# TX.net
KiCad netlist of a schematic drawn in EAGLE
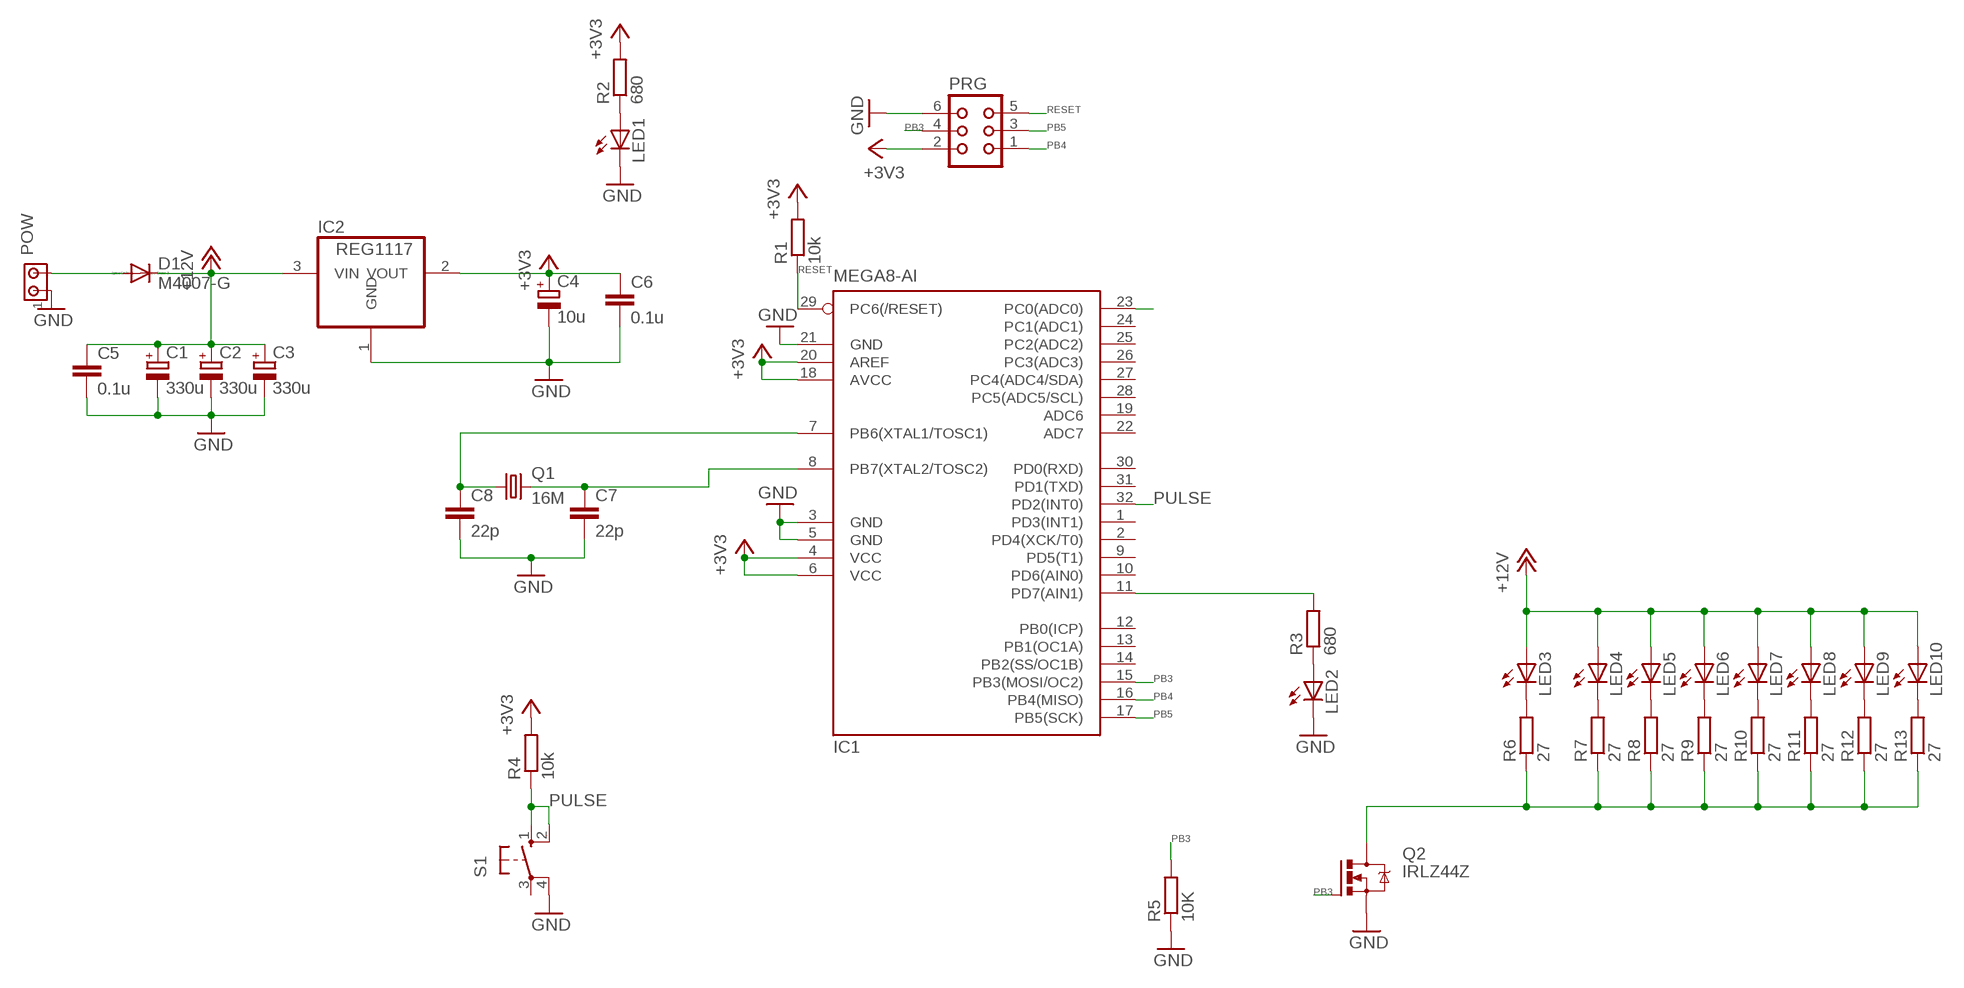
[diagram p0: schematic, sheet 1]

(export (version "E")
  (design (tool "Eeschema 10.0.6"))
  (components
    (comp (ref "C1")
      (value "330u")
      (footprint "eagle-import:140CLH-1010")
      (libsource (lib "eagle-import") (part "CPOL-EU140CLH-1010"))
    )
    (comp (ref "C2")
      (value "330u")
      (footprint "eagle-import:140CLH-1010")
      (libsource (lib "eagle-import") (part "CPOL-EU140CLH-1010"))
    )
    (comp (ref "C3")
      (value "330u")
      (footprint "eagle-import:140CLH-1010")
      (libsource (lib "eagle-import") (part "CPOL-EU140CLH-1010"))
    )
    (comp (ref "C4")
      (value "10u")
      (footprint "eagle-import:140CLH-0810")
      (libsource (lib "eagle-import") (part "CPOL-EU140CLH-0810"))
    )
    (comp (ref "C5")
      (value "0.1u")
      (footprint "eagle-import:C0402")
      (libsource (lib "eagle-import") (part "C-EUC0402"))
    )
    (comp (ref "C6")
      (value "0.1u")
      (footprint "eagle-import:C0402")
      (libsource (lib "eagle-import") (part "C-EUC0402"))
    )
    (comp (ref "C7")
      (value "22p")
      (footprint "eagle-import:C0805")
      (libsource (lib "eagle-import") (part "C-EUC0805"))
    )
    (comp (ref "C8")
      (value "22p")
      (footprint "eagle-import:C0805")
      (libsource (lib "eagle-import") (part "C-EUC0805"))
    )
    (comp (ref "D1")
      (value "M4007-G")
      (footprint "eagle-import:SOD-123_MINI-SMA")
      (libsource (lib "eagle-import") (part "CGRM400-G7"))
    )
    (comp (ref "IC1")
      (value "MEGA8-AI")
      (footprint "eagle-import:TQFP32-08")
      (fields (field (name "MPN") "ATMEGA8-16AU"))
      (libsource (lib "eagle-import") (part "MEGA8-AI"))
    )
    (comp (ref "IC2")
      (value "REG1117")
      (footprint "eagle-import:SOT223")
      (libsource (lib "eagle-import") (part "REG1117"))
    )
    (comp (ref "LED1")
      (value "LED5MM")
      (footprint "eagle-import:LED5MM")
      (libsource (lib "eagle-import") (part "LED5MM"))
    )
    (comp (ref "LED2")
      (value "LED5MM")
      (footprint "eagle-import:LED5MM")
      (libsource (lib "eagle-import") (part "LED5MM"))
    )
    (comp (ref "LED3")
      (value "LED5MM")
      (footprint "eagle-import:LED5MM")
      (libsource (lib "eagle-import") (part "LED5MM"))
    )
    (comp (ref "LED4")
      (value "LED5MM")
      (footprint "eagle-import:LED5MM")
      (libsource (lib "eagle-import") (part "LED5MM"))
    )
    (comp (ref "LED5")
      (value "LED5MM")
      (footprint "eagle-import:LED5MM")
      (libsource (lib "eagle-import") (part "LED5MM"))
    )
    (comp (ref "LED6")
      (value "LED5MM")
      (footprint "eagle-import:LED5MM")
      (libsource (lib "eagle-import") (part "LED5MM"))
    )
    (comp (ref "LED7")
      (value "LED5MM")
      (footprint "eagle-import:LED5MM")
      (libsource (lib "eagle-import") (part "LED5MM"))
    )
    (comp (ref "LED8")
      (value "LED5MM")
      (footprint "eagle-import:LED5MM")
      (libsource (lib "eagle-import") (part "LED5MM"))
    )
    (comp (ref "LED9")
      (value "LED5MM")
      (footprint "eagle-import:LED5MM")
      (libsource (lib "eagle-import") (part "LED5MM"))
    )
    (comp (ref "LED10")
      (value "LED5MM")
      (footprint "eagle-import:LED5MM")
      (libsource (lib "eagle-import") (part "LED5MM"))
    )
    (comp (ref "POW")
      (value "MTA02-100")
      (footprint "eagle-import:10X02MTA")
      (libsource (lib "eagle-import") (part "MTA02-100"))
    )
    (comp (ref "PRG")
      (value "CON06")
      (footprint "eagle-import:CON06")
      (libsource (lib "eagle-import") (part "CON06"))
    )
    (comp (ref "Q1")
      (value "16M")
      (footprint "eagle-import:HC49UP")
      (libsource (lib "eagle-import") (part "CRYSTALHC49UP"))
    )
    (comp (ref "Q2")
      (value "IRLZ44Z")
      (footprint "eagle-import:TO220BH")
      (libsource (lib "eagle-import") (part "IRLZ44Z"))
    )
    (comp (ref "R1")
      (value "10k")
      (footprint "eagle-import:M1206")
      (libsource (lib "eagle-import") (part "R-EU_M1206"))
    )
    (comp (ref "R2")
      (value "680")
      (footprint "eagle-import:M1206")
      (libsource (lib "eagle-import") (part "R-EU_M1206"))
    )
    (comp (ref "R3")
      (value "680")
      (footprint "eagle-import:M1206")
      (libsource (lib "eagle-import") (part "R-EU_M1206"))
    )
    (comp (ref "R4")
      (value "10k")
      (footprint "eagle-import:M1206")
      (libsource (lib "eagle-import") (part "R-EU_M1206"))
    )
    (comp (ref "R5")
      (value "10K")
      (footprint "eagle-import:M1206")
      (libsource (lib "eagle-import") (part "R-EU_M1206"))
    )
    (comp (ref "R6")
      (value "27")
      (footprint "eagle-import:0204_7")
      (libsource (lib "eagle-import") (part "R-EU_0204/7"))
    )
    (comp (ref "R7")
      (value "27")
      (footprint "eagle-import:0204_7")
      (libsource (lib "eagle-import") (part "R-EU_0204/7"))
    )
    (comp (ref "R8")
      (value "27")
      (footprint "eagle-import:0204_7")
      (libsource (lib "eagle-import") (part "R-EU_0204/7"))
    )
    (comp (ref "R9")
      (value "27")
      (footprint "eagle-import:0204_7")
      (libsource (lib "eagle-import") (part "R-EU_0204/7"))
    )
    (comp (ref "R10")
      (value "27")
      (footprint "eagle-import:0204_7")
      (libsource (lib "eagle-import") (part "R-EU_0204/7"))
    )
    (comp (ref "R11")
      (value "27")
      (footprint "eagle-import:0204_7")
      (libsource (lib "eagle-import") (part "R-EU_0204/7"))
    )
    (comp (ref "R12")
      (value "27")
      (footprint "eagle-import:0204_7")
      (libsource (lib "eagle-import") (part "R-EU_0204/7"))
    )
    (comp (ref "R13")
      (value "27")
      (footprint "eagle-import:0204_7")
      (libsource (lib "eagle-import") (part "R-EU_0204/7"))
    )
    (comp (ref "S1")
      (value "10-XX")
      (footprint "eagle-import:B3F-10XX")
      (fields (field (name "MPN") "B3F-1000"))
      (libsource (lib "eagle-import") (part "10-XX"))
    )
  )
  (nets
    (net (code "1") (name "+3V3") (class "Default")
      (node (ref "C4") (pin "+") (pinfunction "+_+") (pintype "passive"))
      (node (ref "C6") (pin "1") (pinfunction "1_1") (pintype "passive"))
      (node (ref "IC1") (pin "18") (pinfunction "AVCC_18") (pintype "power_in"))
      (node (ref "IC1") (pin "20") (pinfunction "AREF_20") (pintype "passive"))
      (node (ref "IC1") (pin "4") (pinfunction "VCC_4") (pintype "power_in"))
      (node (ref "IC1") (pin "6") (pinfunction "VCC_6") (pintype "power_in"))
      (node (ref "IC2") (pin "2") (pinfunction "VOUT_2") (pintype "output"))
      (node (ref "PRG") (pin "2") (pinfunction "2_2") (pintype "passive"))
      (node (ref "R1") (pin "2") (pinfunction "2_2") (pintype "passive"))
      (node (ref "R2") (pin "2") (pinfunction "2_2") (pintype "passive"))
      (node (ref "R4") (pin "2") (pinfunction "2_2") (pintype "passive"))
    )
    (net (code "2") (name "+12V") (class "Default")
      (node (ref "C1") (pin "+") (pinfunction "+_+") (pintype "passive"))
      (node (ref "C2") (pin "+") (pinfunction "+_+") (pintype "passive"))
      (node (ref "C3") (pin "+") (pinfunction "+_+") (pintype "passive"))
      (node (ref "C5") (pin "1") (pinfunction "1_1") (pintype "passive"))
      (node (ref "D1") (pin "C") (pinfunction "C_C") (pintype "passive"))
      (node (ref "IC2") (pin "3") (pinfunction "VIN_3") (pintype "input"))
      (node (ref "LED10") (pin "A") (pinfunction "A_A") (pintype "passive"))
      (node (ref "LED3") (pin "A") (pinfunction "A_A") (pintype "passive"))
      (node (ref "LED4") (pin "A") (pinfunction "A_A") (pintype "passive"))
      (node (ref "LED5") (pin "A") (pinfunction "A_A") (pintype "passive"))
      (node (ref "LED6") (pin "A") (pinfunction "A_A") (pintype "passive"))
      (node (ref "LED7") (pin "A") (pinfunction "A_A") (pintype "passive"))
      (node (ref "LED8") (pin "A") (pinfunction "A_A") (pintype "passive"))
      (node (ref "LED9") (pin "A") (pinfunction "A_A") (pintype "passive"))
    )
    (net (code "3") (name "/PB3") (class "Default")
      (node (ref "IC1") (pin "15") (pinfunction "PB3(MOSI/OC2)_15") (pintype "bidirectional"))
      (node (ref "PRG") (pin "4") (pinfunction "4_4") (pintype "passive"))
      (node (ref "Q2") (pin "G") (pinfunction "G_G") (pintype "passive"))
      (node (ref "R5") (pin "2") (pinfunction "2_2") (pintype "passive"))
    )
    (net (code "4") (name "/PB4") (class "Default")
      (node (ref "IC1") (pin "16") (pinfunction "PB4(MISO)_16") (pintype "bidirectional"))
      (node (ref "PRG") (pin "1") (pinfunction "1_1") (pintype "passive"))
    )
    (net (code "5") (name "/PB5") (class "Default")
      (node (ref "IC1") (pin "17") (pinfunction "PB5(SCK)_17") (pintype "bidirectional"))
      (node (ref "PRG") (pin "3") (pinfunction "3_3") (pintype "passive"))
    )
    (net (code "6") (name "/PULSE") (class "Default")
      (node (ref "IC1") (pin "32") (pinfunction "PD2(INT0)_32") (pintype "bidirectional"))
      (node (ref "R4") (pin "1") (pinfunction "1_1") (pintype "passive"))
      (node (ref "S1") (pin "1") (pinfunction "S_1") (pintype "passive"))
      (node (ref "S1") (pin "2") (pinfunction "S1_2") (pintype "passive"))
    )
    (net (code "7") (name "/RESET") (class "Default")
      (node (ref "IC1") (pin "29") (pinfunction "PC6(/RESET)_29") (pintype "bidirectional"))
      (node (ref "PRG") (pin "5") (pinfunction "5_5") (pintype "passive"))
      (node (ref "R1") (pin "1") (pinfunction "1_1") (pintype "passive"))
    )
    (net (code "8") (name "GND") (class "Default")
      (node (ref "C1") (pin "-") (pinfunction "-_-") (pintype "passive"))
      (node (ref "C2") (pin "-") (pinfunction "-_-") (pintype "passive"))
      (node (ref "C3") (pin "-") (pinfunction "-_-") (pintype "passive"))
      (node (ref "C4") (pin "-") (pinfunction "-_-") (pintype "passive"))
      (node (ref "C5") (pin "2") (pinfunction "2_2") (pintype "passive"))
      (node (ref "C6") (pin "2") (pinfunction "2_2") (pintype "passive"))
      (node (ref "C7") (pin "2") (pinfunction "2_2") (pintype "passive"))
      (node (ref "C8") (pin "2") (pinfunction "2_2") (pintype "passive"))
      (node (ref "IC1") (pin "21") (pinfunction "GND_21") (pintype "power_in"))
      (node (ref "IC1") (pin "3") (pinfunction "GND_3") (pintype "power_in"))
      (node (ref "IC1") (pin "5") (pinfunction "GND_5") (pintype "power_in"))
      (node (ref "IC2") (pin "1") (pinfunction "GND_1") (pintype "power_in"))
      (node (ref "LED1") (pin "K") (pinfunction "C_K") (pintype "passive"))
      (node (ref "LED2") (pin "K") (pinfunction "C_K") (pintype "passive"))
      (node (ref "POW") (pin "1") (pinfunction "1_1") (pintype "passive"))
      (node (ref "PRG") (pin "6") (pinfunction "6_6") (pintype "passive"))
      (node (ref "Q2") (pin "S") (pinfunction "S_S") (pintype "passive"))
      (node (ref "R5") (pin "1") (pinfunction "1_1") (pintype "passive"))
      (node (ref "S1") (pin "4") (pinfunction "P1_4") (pintype "passive"))
    )
    (net (code "9") (name "Net-(D1-PadA)") (class "Default")
      (node (ref "D1") (pin "A") (pinfunction "A_A") (pintype "passive"))
      (node (ref "POW") (pin "2") (pinfunction "2_2") (pintype "passive"))
    )
    (net (code "10") (name "Net-(IC1-PB6(XTAL1{slash}TOSC1))") (class "Default")
      (node (ref "C8") (pin "1") (pinfunction "1_1") (pintype "passive"))
      (node (ref "IC1") (pin "7") (pinfunction "PB6(XTAL1/TOSC1)_7") (pintype "bidirectional"))
      (node (ref "Q1") (pin "1") (pinfunction "1_1") (pintype "passive"))
    )
    (net (code "11") (name "Net-(IC1-PB7(XTAL2{slash}TOSC2))") (class "Default")
      (node (ref "C7") (pin "1") (pinfunction "1_1") (pintype "passive"))
      (node (ref "IC1") (pin "8") (pinfunction "PB7(XTAL2/TOSC2)_8") (pintype "bidirectional"))
      (node (ref "Q1") (pin "2") (pinfunction "2_2") (pintype "passive"))
    )
    (net (code "12") (name "Net-(IC1-PD7(AIN1))") (class "Default")
      (node (ref "IC1") (pin "11") (pinfunction "PD7(AIN1)_11") (pintype "bidirectional"))
      (node (ref "R3") (pin "2") (pinfunction "2_2") (pintype "passive"))
    )
    (net (code "13") (name "Net-(LED1-PadA)") (class "Default")
      (node (ref "LED1") (pin "A") (pinfunction "A_A") (pintype "passive"))
      (node (ref "R2") (pin "1") (pinfunction "1_1") (pintype "passive"))
    )
    (net (code "14") (name "Net-(LED2-PadA)") (class "Default")
      (node (ref "LED2") (pin "A") (pinfunction "A_A") (pintype "passive"))
      (node (ref "R3") (pin "1") (pinfunction "1_1") (pintype "passive"))
    )
    (net (code "15") (name "Net-(LED3-C)") (class "Default")
      (node (ref "LED3") (pin "K") (pinfunction "C_K") (pintype "passive"))
      (node (ref "R6") (pin "2") (pinfunction "2_2") (pintype "passive"))
    )
    (net (code "16") (name "Net-(LED4-C)") (class "Default")
      (node (ref "LED4") (pin "K") (pinfunction "C_K") (pintype "passive"))
      (node (ref "R7") (pin "2") (pinfunction "2_2") (pintype "passive"))
    )
    (net (code "17") (name "Net-(LED5-C)") (class "Default")
      (node (ref "LED5") (pin "K") (pinfunction "C_K") (pintype "passive"))
      (node (ref "R8") (pin "2") (pinfunction "2_2") (pintype "passive"))
    )
    (net (code "18") (name "Net-(LED6-C)") (class "Default")
      (node (ref "LED6") (pin "K") (pinfunction "C_K") (pintype "passive"))
      (node (ref "R9") (pin "2") (pinfunction "2_2") (pintype "passive"))
    )
    (net (code "19") (name "Net-(LED7-C)") (class "Default")
      (node (ref "LED7") (pin "K") (pinfunction "C_K") (pintype "passive"))
      (node (ref "R10") (pin "2") (pinfunction "2_2") (pintype "passive"))
    )
    (net (code "20") (name "Net-(LED8-C)") (class "Default")
      (node (ref "LED8") (pin "K") (pinfunction "C_K") (pintype "passive"))
      (node (ref "R11") (pin "2") (pinfunction "2_2") (pintype "passive"))
    )
    (net (code "21") (name "Net-(LED9-C)") (class "Default")
      (node (ref "LED9") (pin "K") (pinfunction "C_K") (pintype "passive"))
      (node (ref "R12") (pin "2") (pinfunction "2_2") (pintype "passive"))
    )
    (net (code "22") (name "Net-(LED10-C)") (class "Default")
      (node (ref "LED10") (pin "K") (pinfunction "C_K") (pintype "passive"))
      (node (ref "R13") (pin "2") (pinfunction "2_2") (pintype "passive"))
    )
    (net (code "23") (name "Net-(Q2-PadD)") (class "Default")
      (node (ref "Q2") (pin "D") (pinfunction "D_D") (pintype "passive"))
      (node (ref "R10") (pin "1") (pinfunction "1_1") (pintype "passive"))
      (node (ref "R11") (pin "1") (pinfunction "1_1") (pintype "passive"))
      (node (ref "R12") (pin "1") (pinfunction "1_1") (pintype "passive"))
      (node (ref "R13") (pin "1") (pinfunction "1_1") (pintype "passive"))
      (node (ref "R6") (pin "1") (pinfunction "1_1") (pintype "passive"))
      (node (ref "R7") (pin "1") (pinfunction "1_1") (pintype "passive"))
      (node (ref "R8") (pin "1") (pinfunction "1_1") (pintype "passive"))
      (node (ref "R9") (pin "1") (pinfunction "1_1") (pintype "passive"))
    )
    (net (code "24") (name "unconnected-(IC1-ADC6-Pad19)") (class "Default")
      (node (ref "IC1") (pin "19") (pinfunction "ADC6_19") (pintype "bidirectional"))
    )
    (net (code "25") (name "unconnected-(IC1-ADC7-Pad22)") (class "Default")
      (node (ref "IC1") (pin "22") (pinfunction "ADC7_22") (pintype "bidirectional"))
    )
    (net (code "26") (name "unconnected-(IC1-PB0(ICP)-Pad12)") (class "Default")
      (node (ref "IC1") (pin "12") (pinfunction "PB0(ICP)_12") (pintype "bidirectional"))
    )
    (net (code "27") (name "unconnected-(IC1-PB1(OC1A)-Pad13)") (class "Default")
      (node (ref "IC1") (pin "13") (pinfunction "PB1(OC1A)_13") (pintype "bidirectional"))
    )
    (net (code "28") (name "unconnected-(IC1-PB2(SS{slash}OC1B)-Pad14)") (class "Default")
      (node (ref "IC1") (pin "14") (pinfunction "PB2(SS/OC1B)_14") (pintype "bidirectional"))
    )
    (net (code "29") (name "unconnected-(IC1-PC0(ADC0)-Pad23)") (class "Default")
      (node (ref "IC1") (pin "23") (pinfunction "PC0(ADC0)_23") (pintype "bidirectional"))
    )
    (net (code "30") (name "unconnected-(IC1-PC1(ADC1)-Pad24)") (class "Default")
      (node (ref "IC1") (pin "24") (pinfunction "PC1(ADC1)_24") (pintype "bidirectional"))
    )
    (net (code "31") (name "unconnected-(IC1-PC2(ADC2)-Pad25)") (class "Default")
      (node (ref "IC1") (pin "25") (pinfunction "PC2(ADC2)_25") (pintype "bidirectional"))
    )
    (net (code "32") (name "unconnected-(IC1-PC3(ADC3)-Pad26)") (class "Default")
      (node (ref "IC1") (pin "26") (pinfunction "PC3(ADC3)_26") (pintype "bidirectional"))
    )
    (net (code "33") (name "unconnected-(IC1-PC4(ADC4{slash}SDA)-Pad27)") (class "Default")
      (node (ref "IC1") (pin "27") (pinfunction "PC4(ADC4/SDA)_27") (pintype "bidirectional"))
    )
    (net (code "34") (name "unconnected-(IC1-PC5(ADC5{slash}SCL)-Pad28)") (class "Default")
      (node (ref "IC1") (pin "28") (pinfunction "PC5(ADC5/SCL)_28") (pintype "bidirectional"))
    )
    (net (code "35") (name "unconnected-(IC1-PD0(RXD)-Pad30)") (class "Default")
      (node (ref "IC1") (pin "30") (pinfunction "PD0(RXD)_30") (pintype "bidirectional"))
    )
    (net (code "36") (name "unconnected-(IC1-PD1(TXD)-Pad31)") (class "Default")
      (node (ref "IC1") (pin "31") (pinfunction "PD1(TXD)_31") (pintype "bidirectional"))
    )
    (net (code "37") (name "unconnected-(IC1-PD3(INT1)-Pad1)") (class "Default")
      (node (ref "IC1") (pin "1") (pinfunction "PD3(INT1)_1") (pintype "bidirectional"))
    )
    (net (code "38") (name "unconnected-(IC1-PD4(XCK{slash}T0)-Pad2)") (class "Default")
      (node (ref "IC1") (pin "2") (pinfunction "PD4(XCK/T0)_2") (pintype "bidirectional"))
    )
    (net (code "39") (name "unconnected-(IC1-PD5(T1)-Pad9)") (class "Default")
      (node (ref "IC1") (pin "9") (pinfunction "PD5(T1)_9") (pintype "bidirectional"))
    )
    (net (code "40") (name "unconnected-(IC1-PD6(AIN0)-Pad10)") (class "Default")
      (node (ref "IC1") (pin "10") (pinfunction "PD6(AIN0)_10") (pintype "bidirectional"))
    )
    (net (code "41") (name "unconnected-(S1-P-Pad3)") (class "Default")
      (node (ref "S1") (pin "3") (pinfunction "P_3") (pintype "passive"))
    )
  )
)
